# SkyTotalExternal.net
KiCad netlist of a schematic drawn in Altium Designer
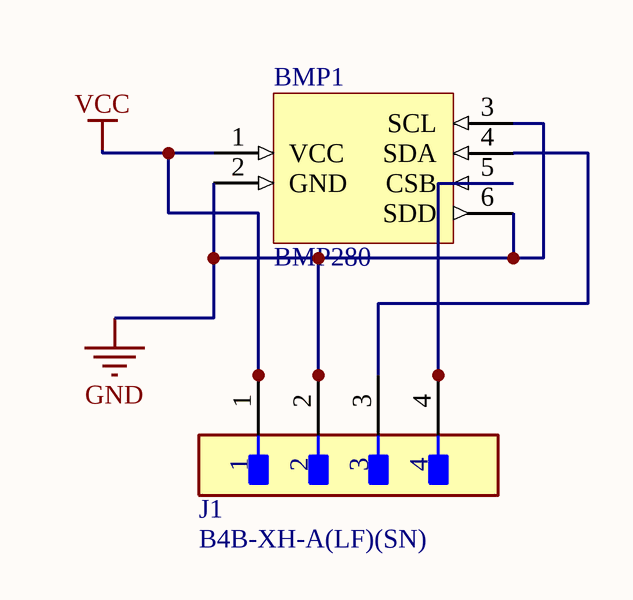
[diagram p0: SkyTotalExternal.SchDoc]

(export (version "E")
  (design (tool "Eeschema 10.0.6"))
  (components
    (comp (ref "BMP1") (value "BMP280") (footprint "BMP280") (libsource (lib "Sky_Schlib") (part "BMP280")))
    (comp (ref "J1")
      (value "B4B-XH-A(LF)(SN)")
      (footprint "FP-B4B-XH-A_LF_SN-MFG")
      (description "CONN HEADER VERT 4POS 2.5MM")
      (libsource (lib "Altium Content Vault") (part "299a8cea1bdcbc3624fe62c390fa72c"))
    )
  )
  (nets
    (net (code "1") (name "GND") (class "Default")
      (node (ref "BMP1") (pin "2") (pinfunction "GND_2") (pintype "input"))
      (node (ref "BMP1") (pin "3") (pinfunction "SCL_3") (pintype "input"))
      (node (ref "BMP1") (pin "6") (pinfunction "SDD_6") (pintype "output"))
      (node (ref "J1") (pin "2") (pinfunction "2_2") (pintype "passive"))
    )
    (net (code "2") (name "Net-(BMP1-CSB)") (class "Default")
      (node (ref "BMP1") (pin "5") (pinfunction "CSB_5") (pintype "input"))
      (node (ref "J1") (pin "4") (pinfunction "4_4") (pintype "passive"))
    )
    (net (code "3") (name "Net-(BMP1-SDA)") (class "Default")
      (node (ref "BMP1") (pin "4") (pinfunction "SDA_4") (pintype "input"))
      (node (ref "J1") (pin "3") (pinfunction "3_3") (pintype "passive"))
    )
    (net (code "4") (name "VCC") (class "Default")
      (node (ref "BMP1") (pin "1") (pinfunction "VCC_1") (pintype "input"))
      (node (ref "J1") (pin "1") (pinfunction "1_1") (pintype "passive"))
    )
  )
)
